# SignalBufferBoard.net
KiCad netlist of a schematic drawn in Altium Designer
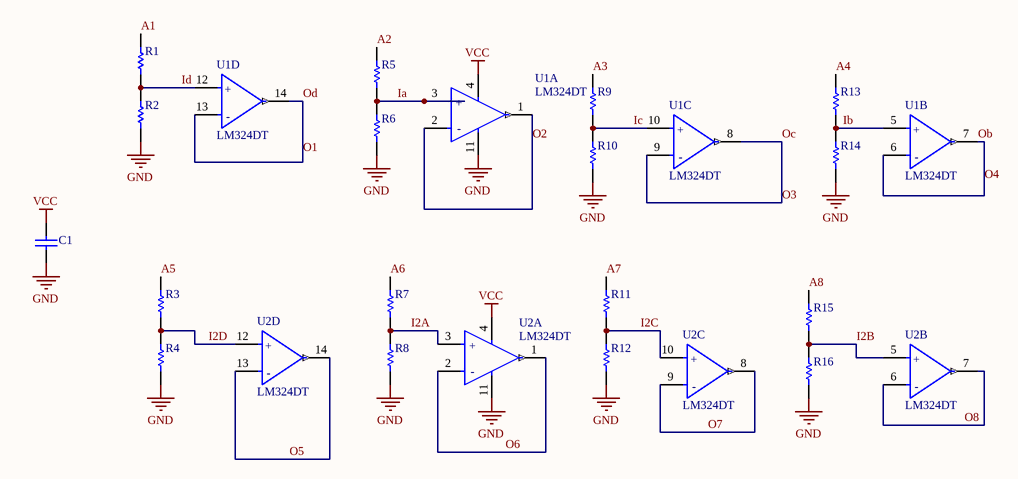
[diagram p0: SignalBufferBoard.SchDoc]

(export (version "E")
  (design (tool "Eeschema 10.0.6"))
  (components
    (comp (ref "C1")
      (value "C0805C105K4PACTU")
      (footprint "CAPC2013X145X50NL20T25")
      (fields (field (name "MANUFACTURER") "Kemet"))
      (libsource (lib "Altium Content Vault") (part "CAP"))
    )
    (comp (ref "R1")
      (value "ERA6AEB104V")
      (footprint "RESC2013X60X40ML20T25")
      (fields (field (name "MANUFACTURER") "Panasonic"))
      (libsource (lib "Altium Content Vault") (part "RES"))
    )
    (comp (ref "R2")
      (value "ERA6AEB204V")
      (footprint "RESC2013X60X40ML20T25")
      (fields (field (name "MANUFACTURER") "Panasonic"))
      (libsource (lib "Altium Content Vault") (part "RES"))
    )
    (comp (ref "R3")
      (value "ERA6AEB104V")
      (footprint "RESC2013X60X40ML20T25")
      (fields (field (name "MANUFACTURER") "Panasonic"))
      (libsource (lib "Altium Content Vault") (part "RES"))
    )
    (comp (ref "R4")
      (value "ERA6AEB204V")
      (footprint "RESC2013X60X40ML20T25")
      (fields (field (name "MANUFACTURER") "Panasonic"))
      (libsource (lib "Altium Content Vault") (part "RES"))
    )
    (comp (ref "R5")
      (value "ERA6AEB104V")
      (footprint "RESC2013X60X40ML20T25")
      (fields (field (name "MANUFACTURER") "Panasonic"))
      (libsource (lib "Altium Content Vault") (part "RES"))
    )
    (comp (ref "R6")
      (value "ERA6AEB204V")
      (footprint "RESC2013X60X40ML20T25")
      (fields (field (name "MANUFACTURER") "Panasonic"))
      (libsource (lib "Altium Content Vault") (part "RES"))
    )
    (comp (ref "R7")
      (value "ERA6AEB104V")
      (footprint "RESC2013X60X40ML20T25")
      (fields (field (name "MANUFACTURER") "Panasonic"))
      (libsource (lib "Altium Content Vault") (part "RES"))
    )
    (comp (ref "R8")
      (value "ERA6AEB204V")
      (footprint "RESC2013X60X40ML20T25")
      (fields (field (name "MANUFACTURER") "Panasonic"))
      (libsource (lib "Altium Content Vault") (part "RES"))
    )
    (comp (ref "R9")
      (value "ERA6AEB104V")
      (footprint "RESC2013X60X40ML20T25")
      (fields (field (name "MANUFACTURER") "Panasonic"))
      (libsource (lib "Altium Content Vault") (part "RES"))
    )
    (comp (ref "R10")
      (value "ERA6AEB204V")
      (footprint "RESC2013X60X40ML20T25")
      (fields (field (name "MANUFACTURER") "Panasonic"))
      (libsource (lib "Altium Content Vault") (part "RES"))
    )
    (comp (ref "R11")
      (value "ERA6AEB104V")
      (footprint "RESC2013X60X40ML20T25")
      (fields (field (name "MANUFACTURER") "Panasonic"))
      (libsource (lib "Altium Content Vault") (part "RES"))
    )
    (comp (ref "R12")
      (value "ERA6AEB204V")
      (footprint "RESC2013X60X40ML20T25")
      (fields (field (name "MANUFACTURER") "Panasonic"))
      (libsource (lib "Altium Content Vault") (part "RES"))
    )
    (comp (ref "R13")
      (value "ERA6AEB104V")
      (footprint "RESC2013X60X40ML20T25")
      (fields (field (name "MANUFACTURER") "Panasonic"))
      (libsource (lib "Altium Content Vault") (part "RES"))
    )
    (comp (ref "R14")
      (value "ERA6AEB204V")
      (footprint "RESC2013X60X40ML20T25")
      (fields (field (name "MANUFACTURER") "Panasonic"))
      (libsource (lib "Altium Content Vault") (part "RES"))
    )
    (comp (ref "R15")
      (value "ERA6AEB104V")
      (footprint "RESC2013X60X40ML20T25")
      (fields (field (name "MANUFACTURER") "Panasonic"))
      (libsource (lib "Altium Content Vault") (part "RES"))
    )
    (comp (ref "R16")
      (value "ERA6AEB204V")
      (footprint "RESC2013X60X40ML20T25")
      (fields (field (name "MANUFACTURER") "Panasonic"))
      (libsource (lib "Altium Content Vault") (part "RES"))
    )
    (comp (ref "U1")
      (value "LM324DT")
      (footprint "FP-SO-14-IPC_A")
      (description "IC OPAMP GP 4 CIRCUIT 14SO")
      (fields
        (field (name "OCTOPART") "https://octopart.com/lm324dt-stmicroelectronics-39579146")
        (field (name "MANUFACTURER") "STMicroelectronics")
      )
      (libsource (lib "Altium Content Vault") (part "a065ef67e5aa9ef3942d43d6008d043"))
    )
    (comp (ref "U2")
      (value "LM324DT")
      (footprint "FP-SO-14-IPC_A")
      (description "IC OPAMP GP 4 CIRCUIT 14SO")
      (fields
        (field (name "OCTOPART") "https://octopart.com/lm324dt-stmicroelectronics-39579146")
        (field (name "MANUFACTURER") "STMicroelectronics")
      )
      (libsource (lib "Altium Content Vault") (part "a065ef67e5aa9ef3942d43d6008d043"))
    )
  )
  (nets
    (net (code "1") (name "/A1") (class "Default")
      (node (ref "R1") (pin "2") (pinfunction "2_2") (pintype "passive"))
    )
    (net (code "2") (name "/A2") (class "Default")
      (node (ref "R5") (pin "2") (pinfunction "2_2") (pintype "passive"))
    )
    (net (code "3") (name "/A3") (class "Default")
      (node (ref "R9") (pin "2") (pinfunction "2_2") (pintype "passive"))
    )
    (net (code "4") (name "/A4") (class "Default")
      (node (ref "R13") (pin "2") (pinfunction "2_2") (pintype "passive"))
    )
    (net (code "5") (name "/A5") (class "Default")
      (node (ref "R3") (pin "2") (pinfunction "2_2") (pintype "passive"))
    )
    (net (code "6") (name "/A6") (class "Default")
      (node (ref "R7") (pin "2") (pinfunction "2_2") (pintype "passive"))
    )
    (net (code "7") (name "/A7") (class "Default")
      (node (ref "R11") (pin "2") (pinfunction "2_2") (pintype "passive"))
    )
    (net (code "8") (name "/A8") (class "Default")
      (node (ref "R15") (pin "2") (pinfunction "2_2") (pintype "passive"))
    )
    (net (code "9") (name "/I2A") (class "Default")
      (node (ref "R7") (pin "1") (pinfunction "1_1") (pintype "passive"))
      (node (ref "R8") (pin "2") (pinfunction "2_2") (pintype "passive"))
      (node (ref "U2") (pin "3") (pinfunction "Non-Inverting_Input_1_3") (pintype "tri_state"))
    )
    (net (code "10") (name "/I2B") (class "Default")
      (node (ref "R15") (pin "1") (pinfunction "1_1") (pintype "passive"))
      (node (ref "R16") (pin "2") (pinfunction "2_2") (pintype "passive"))
      (node (ref "U2") (pin "5") (pinfunction "Non-Inverting_Input_2_5") (pintype "tri_state"))
    )
    (net (code "11") (name "/I2C") (class "Default")
      (node (ref "R11") (pin "1") (pinfunction "1_1") (pintype "passive"))
      (node (ref "R12") (pin "2") (pinfunction "2_2") (pintype "passive"))
      (node (ref "U2") (pin "10") (pinfunction "Non-Inverting_Input_3_10") (pintype "tri_state"))
    )
    (net (code "12") (name "/I2D") (class "Default")
      (node (ref "R3") (pin "1") (pinfunction "1_1") (pintype "passive"))
      (node (ref "R4") (pin "2") (pinfunction "2_2") (pintype "passive"))
      (node (ref "U2") (pin "12") (pinfunction "Non-Inverting_Input_4_12") (pintype "tri_state"))
    )
    (net (code "13") (name "/Ia") (class "Default")
      (node (ref "R5") (pin "1") (pinfunction "1_1") (pintype "passive"))
      (node (ref "R6") (pin "2") (pinfunction "2_2") (pintype "passive"))
      (node (ref "U1") (pin "3") (pinfunction "Non-Inverting_Input_1_3") (pintype "tri_state"))
    )
    (net (code "14") (name "/Ib") (class "Default")
      (node (ref "R13") (pin "1") (pinfunction "1_1") (pintype "passive"))
      (node (ref "R14") (pin "2") (pinfunction "2_2") (pintype "passive"))
      (node (ref "U1") (pin "5") (pinfunction "Non-Inverting_Input_2_5") (pintype "tri_state"))
    )
    (net (code "15") (name "/Ic") (class "Default")
      (node (ref "R10") (pin "2") (pinfunction "2_2") (pintype "passive"))
      (node (ref "R9") (pin "1") (pinfunction "1_1") (pintype "passive"))
      (node (ref "U1") (pin "10") (pinfunction "Non-Inverting_Input_3_10") (pintype "tri_state"))
    )
    (net (code "16") (name "/Id") (class "Default")
      (node (ref "R1") (pin "1") (pinfunction "1_1") (pintype "passive"))
      (node (ref "R2") (pin "2") (pinfunction "2_2") (pintype "passive"))
      (node (ref "U1") (pin "12") (pinfunction "Non-Inverting_Input_4_12") (pintype "tri_state"))
    )
    (net (code "17") (name "/O1") (class "Default")
      (node (ref "U1") (pin "13") (pinfunction "Inverting_Input_4_13") (pintype "tri_state"))
      (node (ref "U1") (pin "14") (pinfunction "Output_4_14") (pintype "output"))
    )
    (net (code "18") (name "/O2") (class "Default")
      (node (ref "U1") (pin "1") (pinfunction "Output_1_1") (pintype "output"))
      (node (ref "U1") (pin "2") (pinfunction "Inverting_Input_1_2") (pintype "tri_state"))
    )
    (net (code "19") (name "/O3") (class "Default")
      (node (ref "U1") (pin "8") (pinfunction "Output_3_8") (pintype "output"))
      (node (ref "U1") (pin "9") (pinfunction "Inverting_Input_3_9") (pintype "tri_state"))
    )
    (net (code "20") (name "/O4") (class "Default")
      (node (ref "U1") (pin "6") (pinfunction "Inverting_Input_2_6") (pintype "tri_state"))
      (node (ref "U1") (pin "7") (pinfunction "Output_2_7") (pintype "output"))
    )
    (net (code "21") (name "/O5") (class "Default")
      (node (ref "U2") (pin "13") (pinfunction "Inverting_Input_4_13") (pintype "tri_state"))
      (node (ref "U2") (pin "14") (pinfunction "Output_4_14") (pintype "output"))
    )
    (net (code "22") (name "/O6") (class "Default")
      (node (ref "U2") (pin "1") (pinfunction "Output_1_1") (pintype "output"))
      (node (ref "U2") (pin "2") (pinfunction "Inverting_Input_1_2") (pintype "tri_state"))
    )
    (net (code "23") (name "/O7") (class "Default")
      (node (ref "U2") (pin "8") (pinfunction "Output_3_8") (pintype "output"))
      (node (ref "U2") (pin "9") (pinfunction "Inverting_Input_3_9") (pintype "tri_state"))
    )
    (net (code "24") (name "/O8") (class "Default")
      (node (ref "U2") (pin "6") (pinfunction "Inverting_Input_2_6") (pintype "tri_state"))
      (node (ref "U2") (pin "7") (pinfunction "Output_2_7") (pintype "output"))
    )
    (net (code "25") (name "GND") (class "Default")
      (node (ref "C1") (pin "1") (pinfunction "1_1") (pintype "passive"))
      (node (ref "R10") (pin "1") (pinfunction "1_1") (pintype "passive"))
      (node (ref "R12") (pin "1") (pinfunction "1_1") (pintype "passive"))
      (node (ref "R14") (pin "1") (pinfunction "1_1") (pintype "passive"))
      (node (ref "R16") (pin "1") (pinfunction "1_1") (pintype "passive"))
      (node (ref "R2") (pin "1") (pinfunction "1_1") (pintype "passive"))
      (node (ref "R4") (pin "1") (pinfunction "1_1") (pintype "passive"))
      (node (ref "R6") (pin "1") (pinfunction "1_1") (pintype "passive"))
      (node (ref "R8") (pin "1") (pinfunction "1_1") (pintype "passive"))
      (node (ref "U1") (pin "11") (pinfunction "VCC-_11") (pintype "power_in"))
      (node (ref "U2") (pin "11") (pinfunction "VCC-_11") (pintype "power_in"))
    )
    (net (code "26") (name "VCC") (class "Default")
      (node (ref "C1") (pin "2") (pinfunction "2_2") (pintype "passive"))
      (node (ref "U1") (pin "4") (pinfunction "VCC+_4") (pintype "power_in"))
      (node (ref "U2") (pin "4") (pinfunction "VCC+_4") (pintype "power_in"))
    )
  )
)
